# Page-7.net
KiCad netlist of a schematic drawn in Altium Designer
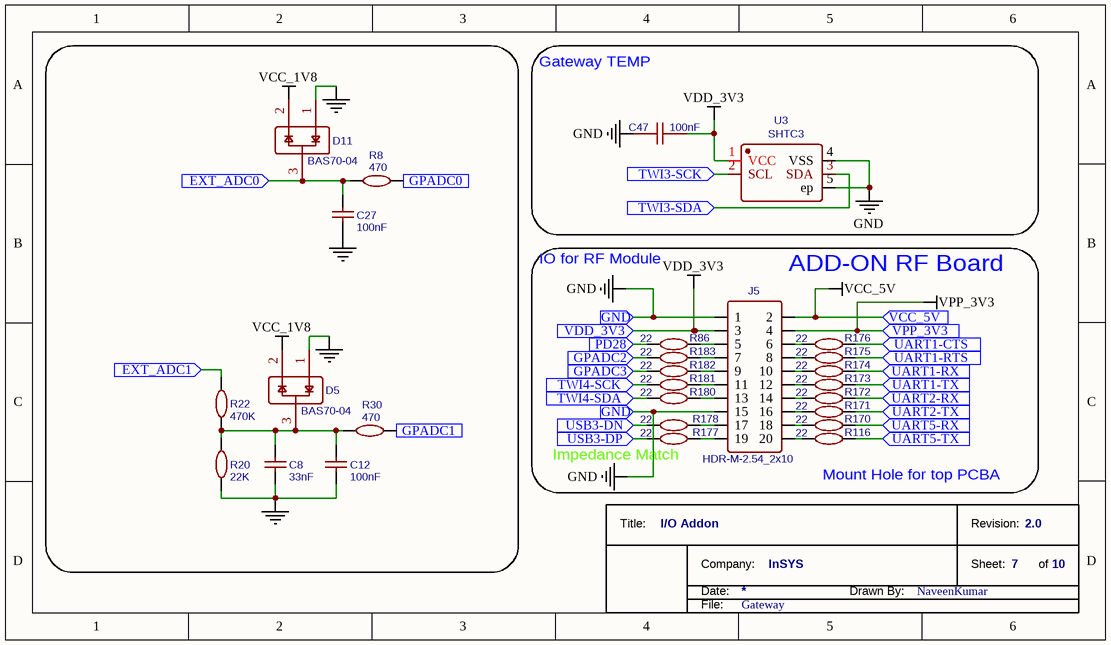
[diagram p0: Page-7.schdoc]

(export (version "E")
  (design (tool "Eeschema 10.0.6"))
  (components
    (comp (ref "*")
      (value "TitleBlock_1")
      (description "TitleBlock  No-2")
      (fields (field (name "DRAWN BY") "*"))
      (libsource (lib "GateWay_AllwinnerV2") (part "TitleBlock_1"))
    )
    (comp (ref "C8")
      (value "33nF")
      (footprint "GWAY_Capacitor_0603")
      (fields (field (name "MANUFACTURER PART") "CL10B333KB8NNNC") (field (name "MANUFACTURER") "SAMSUNG"))
      (libsource (lib "altium-import") (part "root_1_33nF_"))
    )
    (comp (ref "C12")
      (value "100nF")
      (footprint "GWAY_Capacitor_0603")
      (fields (field (name "MANUFACTURER PART") "CL10F104ZB8NNNC") (field (name "MANUFACTURER") "SAMSUNG"))
      (libsource (lib "altium-import") (part "root_1_100nF_"))
    )
    (comp (ref "C27")
      (value "100nF")
      (footprint "GWAY_Capacitor_0603")
      (fields (field (name "MANUFACTURER PART") "CL10F104ZB8NNNC") (field (name "MANUFACTURER") "SAMSUNG"))
      (libsource (lib "altium-import") (part "root_1_100nF_"))
    )
    (comp (ref "C47")
      (value "100nF")
      (footprint "GWAY_Capacitor_0603")
      (fields (field (name "MANUFACTURER") "SAMSUNG") (field (name "MANUFACTURER PART") "CL10B104KB8NNNC"))
      (libsource (lib "altium-import") (part "root_0_100nF_"))
    )
    (comp (ref "D5")
      (value "BAS70-04")
      (footprint "GWAY_SOT23-3PIN")
      (fields (field (name "MANUFACTURER") "CJ") (field (name "CONTRIBUTOR") "LCSC"))
      (libsource (lib "altium-import") (part "root_2_BAS70-04_"))
    )
    (comp (ref "D11")
      (value "BAS70-04")
      (footprint "GWAY_SOT23-3PIN")
      (fields (field (name "MANUFACTURER") "CJ") (field (name "CONTRIBUTOR") "LCSC"))
      (libsource (lib "altium-import") (part "root_2_BAS70-04_"))
    )
    (comp (ref "J5")
      (value "HDR-M-2.54_2x10")
      (footprint "GWAY_2x10way_HEADER_CONN")
      (fields (field (name "CONTRIBUTOR") "LCEDA_Lib"))
      (libsource (lib "altium-import") (part "root_0_HDR-M-2.54_2x10_"))
    )
    (comp (ref "R8")
      (value "470")
      (footprint "GWAY_Resistor_0603")
      (fields (field (name "MANUFACTURER") "YAGEO") (field (name "MANUFACTURER PART") "RC0603FR-07470RL"))
      (libsource (lib "altium-import") (part "root_0_470_"))
    )
    (comp (ref "R20")
      (value "22K")
      (footprint "GWAY_Resistor_0805")
      (fields (field (name "MANUFACTURER") "YAGEO") (field (name "MANUFACTURER PART") "RC0805JR-0722KL"))
      (libsource (lib "altium-import") (part "root_1_22K_"))
    )
    (comp (ref "R22")
      (value "470K")
      (footprint "GWAY_Resistor_0603")
      (fields (field (name "MANUFACTURER") "YAGEO") (field (name "MANUFACTURER PART") "RC0603FR-07470KL"))
      (libsource (lib "altium-import") (part "root_1_470K_"))
    )
    (comp (ref "R30")
      (value "470")
      (footprint "GWAY_Resistor_0603")
      (fields (field (name "MANUFACTURER") "YAGEO") (field (name "MANUFACTURER PART") "RC0603FR-07470RL"))
      (libsource (lib "altium-import") (part "root_0_470_"))
    )
    (comp (ref "R86")
      (value "22")
      (footprint "GWAY_Resistor_0603")
      (fields (field (name "MANUFACTURER") "YAGEO") (field (name "MANUFACTURER PART") "RC0603FR-0722RL"))
      (libsource (lib "altium-import") (part "root_0_22_"))
    )
    (comp (ref "R116")
      (value "22")
      (footprint "GWAY_Resistor_0603")
      (fields (field (name "MANUFACTURER") "YAGEO") (field (name "MANUFACTURER PART") "RC0603FR-0722RL"))
      (libsource (lib "altium-import") (part "root_0_22_"))
    )
    (comp (ref "R170")
      (value "22")
      (footprint "GWAY_Resistor_0603")
      (fields (field (name "MANUFACTURER") "YAGEO") (field (name "MANUFACTURER PART") "RC0603FR-0722RL"))
      (libsource (lib "altium-import") (part "root_0_22_"))
    )
    (comp (ref "R171")
      (value "22")
      (footprint "GWAY_Resistor_0603")
      (fields (field (name "MANUFACTURER") "YAGEO") (field (name "MANUFACTURER PART") "RC0603FR-0722RL"))
      (libsource (lib "altium-import") (part "root_0_22_"))
    )
    (comp (ref "R172")
      (value "22")
      (footprint "GWAY_Resistor_0603")
      (fields (field (name "MANUFACTURER") "YAGEO") (field (name "MANUFACTURER PART") "RC0603FR-0722RL"))
      (libsource (lib "altium-import") (part "root_0_22_"))
    )
    (comp (ref "R173")
      (value "22")
      (footprint "GWAY_Resistor_0603")
      (fields (field (name "MANUFACTURER") "YAGEO") (field (name "MANUFACTURER PART") "RC0603FR-0722RL"))
      (libsource (lib "altium-import") (part "root_0_22_"))
    )
    (comp (ref "R174")
      (value "22")
      (footprint "GWAY_Resistor_0603")
      (fields (field (name "MANUFACTURER") "YAGEO") (field (name "MANUFACTURER PART") "RC0603FR-0722RL"))
      (libsource (lib "altium-import") (part "root_0_22_"))
    )
    (comp (ref "R175")
      (value "22")
      (footprint "GWAY_Resistor_0603")
      (fields (field (name "MANUFACTURER") "YAGEO") (field (name "MANUFACTURER PART") "RC0603FR-0722RL"))
      (libsource (lib "altium-import") (part "root_0_22_"))
    )
    (comp (ref "R176")
      (value "22")
      (footprint "GWAY_Resistor_0603")
      (fields (field (name "MANUFACTURER") "YAGEO") (field (name "MANUFACTURER PART") "RC0603FR-0722RL"))
      (libsource (lib "altium-import") (part "root_0_22_"))
    )
    (comp (ref "R177")
      (value "22")
      (footprint "GWAY_Resistor_0603")
      (fields (field (name "MANUFACTURER") "YAGEO") (field (name "MANUFACTURER PART") "RC0603FR-0722RL"))
      (libsource (lib "altium-import") (part "root_0_22_"))
    )
    (comp (ref "R178")
      (value "22")
      (footprint "GWAY_Resistor_0603")
      (fields (field (name "MANUFACTURER") "YAGEO") (field (name "MANUFACTURER PART") "RC0603FR-0722RL"))
      (libsource (lib "altium-import") (part "root_0_22_"))
    )
    (comp (ref "R180")
      (value "22")
      (footprint "GWAY_Resistor_0603")
      (fields (field (name "MANUFACTURER") "YAGEO") (field (name "MANUFACTURER PART") "RC0603FR-0722RL"))
      (libsource (lib "altium-import") (part "root_0_22_"))
    )
    (comp (ref "R181")
      (value "22")
      (footprint "GWAY_Resistor_0603")
      (fields (field (name "MANUFACTURER") "YAGEO") (field (name "MANUFACTURER PART") "RC0603FR-0722RL"))
      (libsource (lib "altium-import") (part "root_0_22_"))
    )
    (comp (ref "R182")
      (value "22")
      (footprint "GWAY_Resistor_0603")
      (fields (field (name "MANUFACTURER") "YAGEO") (field (name "MANUFACTURER PART") "RC0603FR-0722RL"))
      (libsource (lib "altium-import") (part "root_0_22_"))
    )
    (comp (ref "R183")
      (value "22")
      (footprint "GWAY_Resistor_0603")
      (fields (field (name "MANUFACTURER") "YAGEO") (field (name "MANUFACTURER PART") "RC0603FR-0722RL"))
      (libsource (lib "altium-import") (part "root_0_22_"))
    )
    (comp (ref "U3")
      (value "SHTC3")
      (footprint "GWAY_DFN4_SHTC3")
      (fields (field (name "MANUFACTURER") "Sensirion(瑞士盛思锐)") (field (name "CONTRIBUTOR") "LCSC"))
      (libsource (lib "altium-import") (part "root_0_SHTC3_"))
    )
  )
  (nets
    (net (code "1") (name "/EXT_ADC0") (class "Default")
      (node (ref "C27") (pin "2") (pinfunction "2_2") (pintype "passive"))
      (node (ref "D11") (pin "3") (pinfunction "3_3") (pintype "passive"))
      (node (ref "R8") (pin "1") (pinfunction "1_1") (pintype "passive"))
    )
    (net (code "2") (name "/EXT_ADC1") (class "Default")
      (node (ref "R22") (pin "2") (pinfunction "2_2") (pintype "passive"))
    )
    (net (code "3") (name "/GPADC0") (class "Default")
      (node (ref "R8") (pin "2") (pinfunction "2_2") (pintype "passive"))
    )
    (net (code "4") (name "/GPADC1") (class "Default")
      (node (ref "R30") (pin "2") (pinfunction "2_2") (pintype "passive"))
    )
    (net (code "5") (name "/GPADC2") (class "Default")
      (node (ref "R183") (pin "1") (pinfunction "1_1") (pintype "passive"))
    )
    (net (code "6") (name "/GPADC3") (class "Default")
      (node (ref "R182") (pin "1") (pinfunction "1_1") (pintype "passive"))
    )
    (net (code "7") (name "/PD28") (class "Default")
      (node (ref "R86") (pin "1") (pinfunction "1_1") (pintype "passive"))
    )
    (net (code "8") (name "/TWI3-SCK") (class "Default")
      (node (ref "U3") (pin "2") (pinfunction "SCL_2") (pintype "passive"))
    )
    (net (code "9") (name "/TWI3-SDA") (class "Default")
      (node (ref "U3") (pin "3") (pinfunction "SDA_3") (pintype "passive"))
    )
    (net (code "10") (name "/TWI4-SCK") (class "Default")
      (node (ref "R181") (pin "1") (pinfunction "1_1") (pintype "passive"))
    )
    (net (code "11") (name "/TWI4-SDA") (class "Default")
      (node (ref "R180") (pin "1") (pinfunction "1_1") (pintype "passive"))
    )
    (net (code "12") (name "/UART1-CTS") (class "Default")
      (node (ref "R176") (pin "2") (pinfunction "2_2") (pintype "passive"))
    )
    (net (code "13") (name "/UART1-RTS") (class "Default")
      (node (ref "R175") (pin "2") (pinfunction "2_2") (pintype "passive"))
    )
    (net (code "14") (name "/UART1-RX") (class "Default")
      (node (ref "R174") (pin "2") (pinfunction "2_2") (pintype "passive"))
    )
    (net (code "15") (name "/UART1-TX") (class "Default")
      (node (ref "R173") (pin "2") (pinfunction "2_2") (pintype "passive"))
    )
    (net (code "16") (name "/UART2-RX") (class "Default")
      (node (ref "R172") (pin "2") (pinfunction "2_2") (pintype "passive"))
    )
    (net (code "17") (name "/UART2-TX") (class "Default")
      (node (ref "R171") (pin "2") (pinfunction "2_2") (pintype "passive"))
    )
    (net (code "18") (name "/UART5-RX") (class "Default")
      (node (ref "R170") (pin "2") (pinfunction "2_2") (pintype "passive"))
    )
    (net (code "19") (name "/UART5-TX") (class "Default")
      (node (ref "R116") (pin "2") (pinfunction "2_2") (pintype "passive"))
    )
    (net (code "20") (name "/USB3-DN") (class "Default")
      (node (ref "R178") (pin "1") (pinfunction "1_1") (pintype "passive"))
    )
    (net (code "21") (name "/USB3-DP") (class "Default")
      (node (ref "R177") (pin "1") (pinfunction "1_1") (pintype "passive"))
    )
    (net (code "22") (name "GND") (class "Default")
      (node (ref "C12") (pin "1") (pinfunction "1_1") (pintype "passive"))
      (node (ref "C27") (pin "1") (pinfunction "1_1") (pintype "passive"))
      (node (ref "C47") (pin "1") (pinfunction "1_1") (pintype "passive"))
      (node (ref "C8") (pin "1") (pinfunction "1_1") (pintype "passive"))
      (node (ref "D11") (pin "1") (pinfunction "1_1") (pintype "passive"))
      (node (ref "D5") (pin "1") (pinfunction "1_1") (pintype "passive"))
      (node (ref "J5") (pin "1") (pinfunction "1_1") (pintype "passive"))
      (node (ref "J5") (pin "15") (pinfunction "15_15") (pintype "passive"))
      (node (ref "R20") (pin "1") (pinfunction "1_1") (pintype "passive"))
      (node (ref "U3") (pin "4") (pinfunction "VSS_4") (pintype "passive"))
      (node (ref "U3") (pin "5") (pinfunction "ep_5") (pintype "passive"))
    )
    (net (code "23") (name "Net-(C12-Pad2)") (class "Default")
      (node (ref "C12") (pin "2") (pinfunction "2_2") (pintype "passive"))
      (node (ref "C8") (pin "2") (pinfunction "2_2") (pintype "passive"))
      (node (ref "D5") (pin "3") (pinfunction "3_3") (pintype "passive"))
      (node (ref "R20") (pin "2") (pinfunction "2_2") (pintype "passive"))
      (node (ref "R22") (pin "1") (pinfunction "1_1") (pintype "passive"))
      (node (ref "R30") (pin "1") (pinfunction "1_1") (pintype "passive"))
    )
    (net (code "24") (name "Net-(J5-Pad5)") (class "Default")
      (node (ref "J5") (pin "5") (pinfunction "5_5") (pintype "passive"))
      (node (ref "R86") (pin "2") (pinfunction "2_2") (pintype "passive"))
    )
    (net (code "25") (name "Net-(J5-Pad6)") (class "Default")
      (node (ref "J5") (pin "6") (pinfunction "6_6") (pintype "passive"))
      (node (ref "R176") (pin "1") (pinfunction "1_1") (pintype "passive"))
    )
    (net (code "26") (name "Net-(J5-Pad7)") (class "Default")
      (node (ref "J5") (pin "7") (pinfunction "7_7") (pintype "passive"))
      (node (ref "R183") (pin "2") (pinfunction "2_2") (pintype "passive"))
    )
    (net (code "27") (name "Net-(J5-Pad8)") (class "Default")
      (node (ref "J5") (pin "8") (pinfunction "8_8") (pintype "passive"))
      (node (ref "R175") (pin "1") (pinfunction "1_1") (pintype "passive"))
    )
    (net (code "28") (name "Net-(J5-Pad9)") (class "Default")
      (node (ref "J5") (pin "9") (pinfunction "9_9") (pintype "passive"))
      (node (ref "R182") (pin "2") (pinfunction "2_2") (pintype "passive"))
    )
    (net (code "29") (name "Net-(J5-Pad10)") (class "Default")
      (node (ref "J5") (pin "10") (pinfunction "10_10") (pintype "passive"))
      (node (ref "R174") (pin "1") (pinfunction "1_1") (pintype "passive"))
    )
    (net (code "30") (name "Net-(J5-Pad11)") (class "Default")
      (node (ref "J5") (pin "11") (pinfunction "11_11") (pintype "passive"))
      (node (ref "R181") (pin "2") (pinfunction "2_2") (pintype "passive"))
    )
    (net (code "31") (name "Net-(J5-Pad12)") (class "Default")
      (node (ref "J5") (pin "12") (pinfunction "12_12") (pintype "passive"))
      (node (ref "R173") (pin "1") (pinfunction "1_1") (pintype "passive"))
    )
    (net (code "32") (name "Net-(J5-Pad13)") (class "Default")
      (node (ref "J5") (pin "13") (pinfunction "13_13") (pintype "passive"))
      (node (ref "R180") (pin "2") (pinfunction "2_2") (pintype "passive"))
    )
    (net (code "33") (name "Net-(J5-Pad14)") (class "Default")
      (node (ref "J5") (pin "14") (pinfunction "14_14") (pintype "passive"))
      (node (ref "R172") (pin "1") (pinfunction "1_1") (pintype "passive"))
    )
    (net (code "34") (name "Net-(J5-Pad16)") (class "Default")
      (node (ref "J5") (pin "16") (pinfunction "16_16") (pintype "passive"))
      (node (ref "R171") (pin "1") (pinfunction "1_1") (pintype "passive"))
    )
    (net (code "35") (name "Net-(J5-Pad17)") (class "Default")
      (node (ref "J5") (pin "17") (pinfunction "17_17") (pintype "passive"))
      (node (ref "R178") (pin "2") (pinfunction "2_2") (pintype "passive"))
    )
    (net (code "36") (name "Net-(J5-Pad18)") (class "Default")
      (node (ref "J5") (pin "18") (pinfunction "18_18") (pintype "passive"))
      (node (ref "R170") (pin "1") (pinfunction "1_1") (pintype "passive"))
    )
    (net (code "37") (name "Net-(J5-Pad19)") (class "Default")
      (node (ref "J5") (pin "19") (pinfunction "19_19") (pintype "passive"))
      (node (ref "R177") (pin "2") (pinfunction "2_2") (pintype "passive"))
    )
    (net (code "38") (name "Net-(J5-Pad20)") (class "Default")
      (node (ref "J5") (pin "20") (pinfunction "20_20") (pintype "passive"))
      (node (ref "R116") (pin "1") (pinfunction "1_1") (pintype "passive"))
    )
    (net (code "39") (name "VCC_1V8") (class "Default")
      (node (ref "D11") (pin "2") (pinfunction "2_2") (pintype "passive"))
      (node (ref "D5") (pin "2") (pinfunction "2_2") (pintype "passive"))
    )
    (net (code "40") (name "VCC_5V") (class "Default")
      (node (ref "J5") (pin "2") (pinfunction "2_2") (pintype "passive"))
    )
    (net (code "41") (name "VDD_3V3") (class "Default")
      (node (ref "C47") (pin "2") (pinfunction "2_2") (pintype "passive"))
      (node (ref "J5") (pin "3") (pinfunction "3_3") (pintype "passive"))
      (node (ref "U3") (pin "1") (pinfunction "VCC_1") (pintype "passive"))
    )
    (net (code "42") (name "VPP_3V3") (class "Default")
      (node (ref "J5") (pin "4") (pinfunction "4_4") (pintype "passive"))
    )
  )
)
